# Ind_current_sensor_VW.net
KiCad netlist of a schematic drawn in Altium Designer
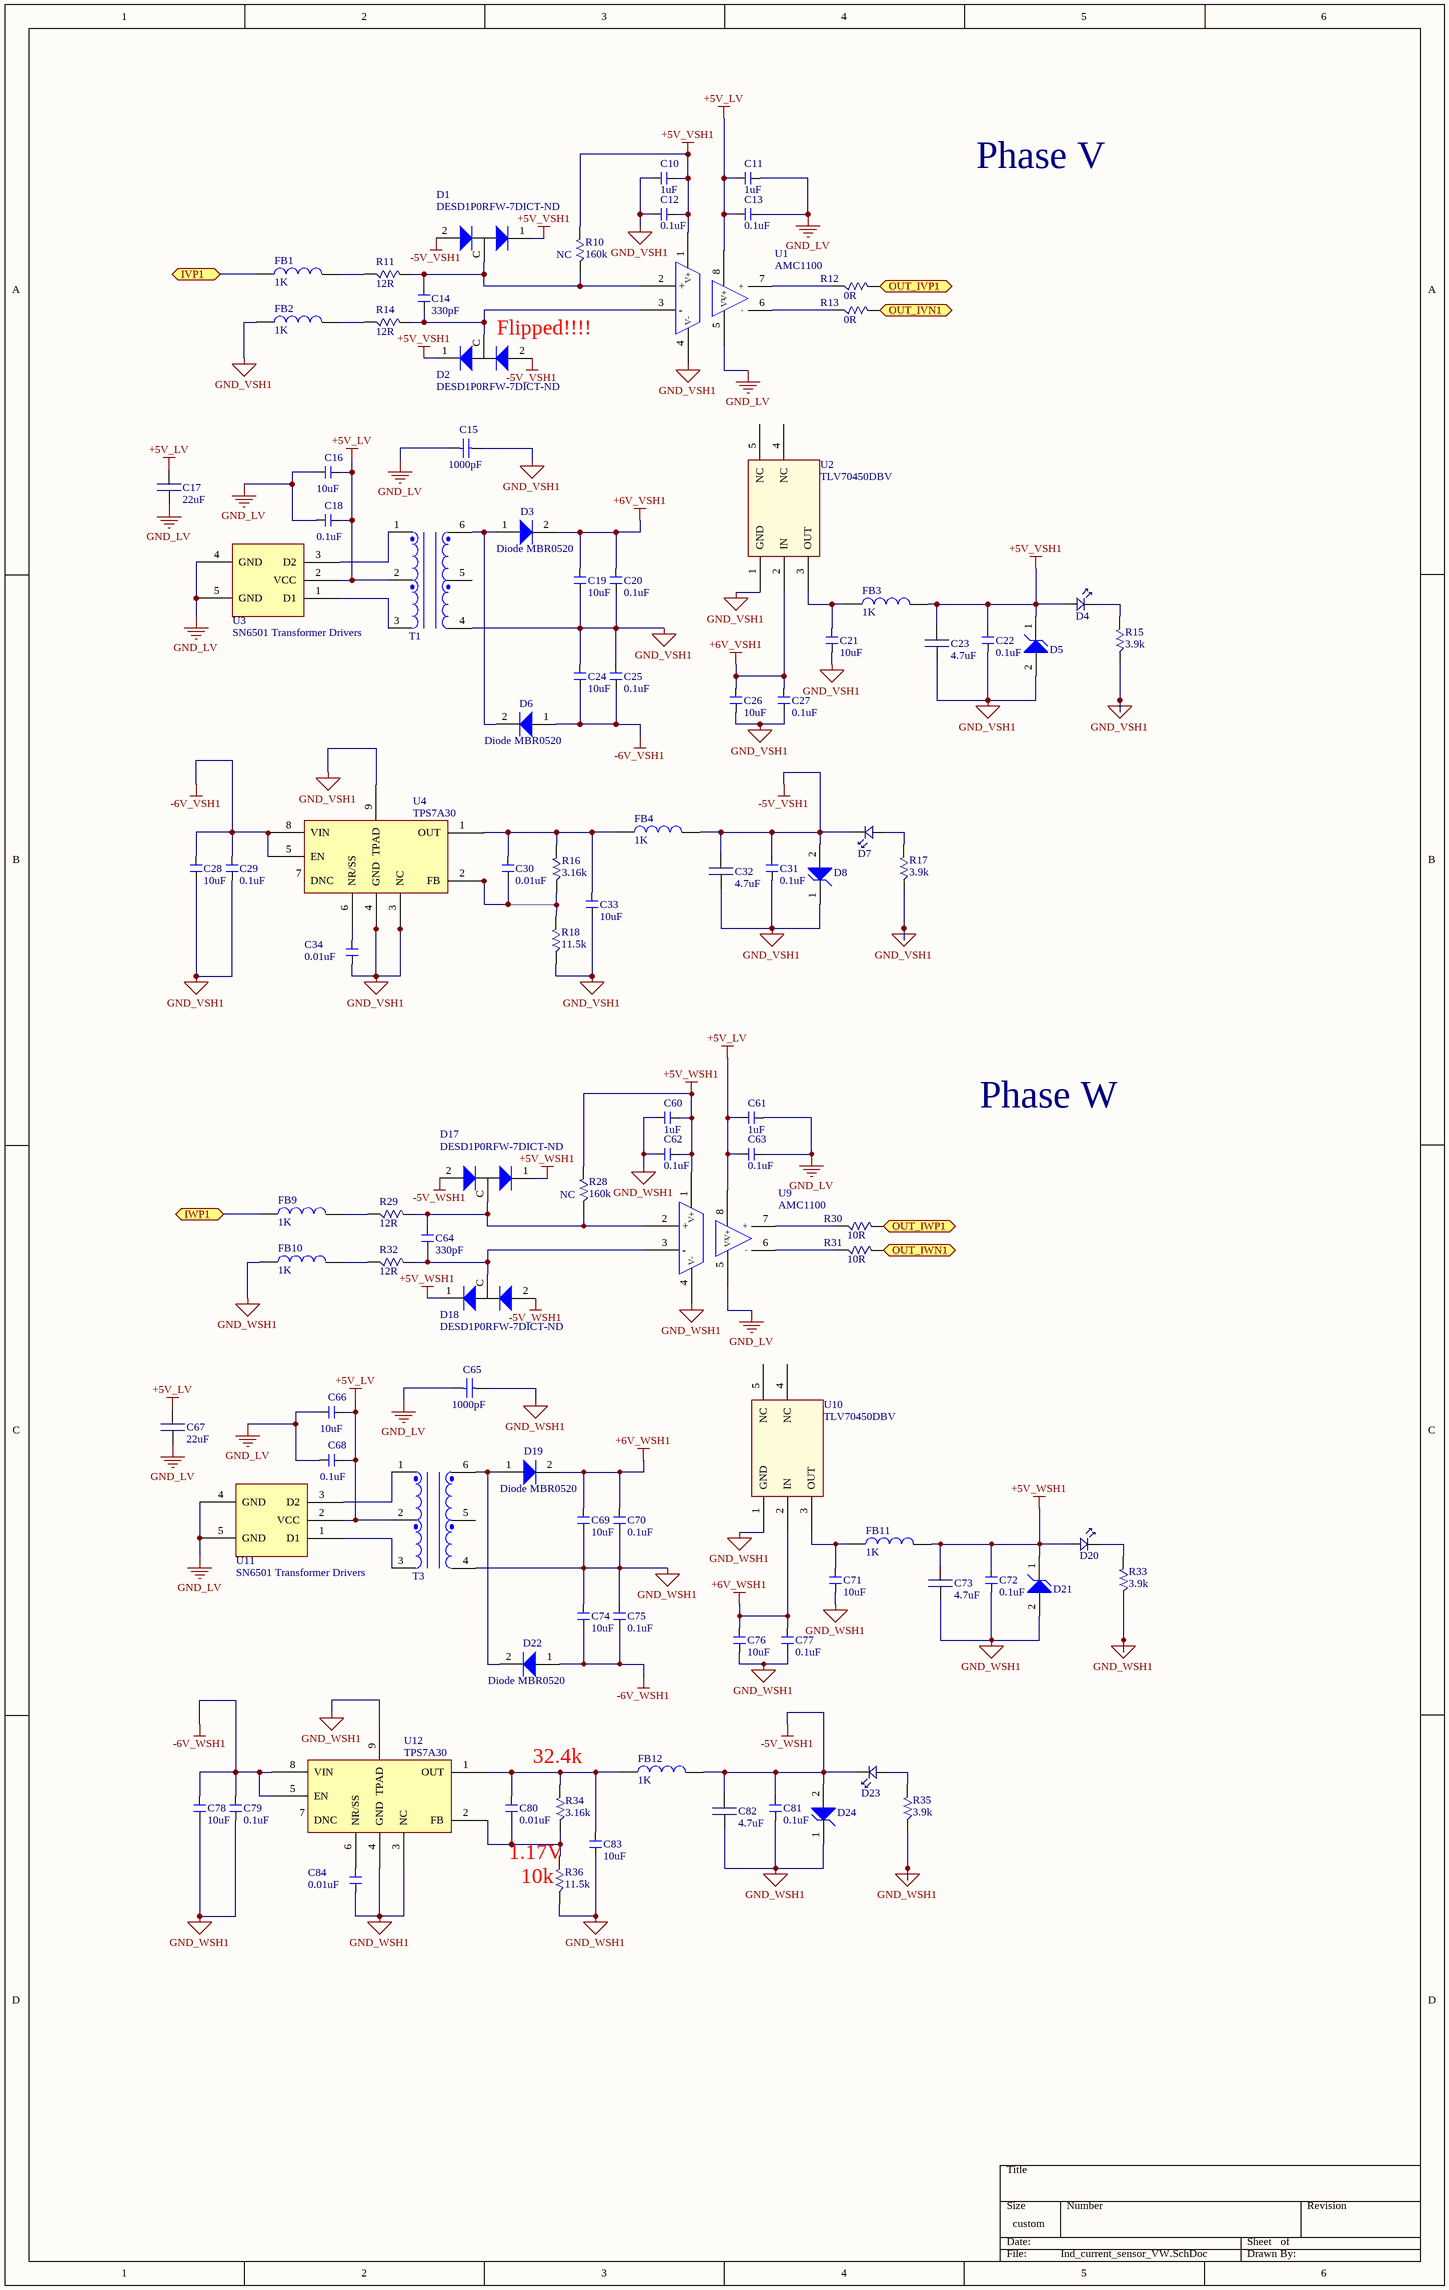
[diagram p0: Ind_current_sensor_VW.SchDoc]

(export (version "E")
  (design (tool "Eeschema 10.0.6"))
  (components
    (comp (ref "C10")
      (value "1uF")
      (footprint "0603 (1608 Metric)")
      (description "CAP CER 1UF 50V X5R 0603")
      (fields (field (name "PART") "1276-1860-1-ND") (field (name "Comment") "Cap 0603_new"))
      (libsource (lib "Library_Microgrid") (part "Cap 0603_new"))
    )
    (comp (ref "C11")
      (value "1uF")
      (footprint "0603 (1608 Metric)")
      (description "CAP CER 1UF 50V X5R 0603")
      (fields (field (name "PART") "1276-1860-1-ND") (field (name "Comment") "Cap 0603_new"))
      (libsource (lib "Library_Microgrid") (part "Cap 0603_new"))
    )
    (comp (ref "C12")
      (value "0.1uF")
      (footprint "0603 (1608 Metric)")
      (description "CAP CER 0.1UF 50V Y5V 0603")
      (fields (field (name "PART") "311-1343-6-ND") (field (name "Comment") "Cap 0603_new"))
      (libsource (lib "Library_Microgrid") (part "Cap 0603_new"))
    )
    (comp (ref "C13")
      (value "0.1uF")
      (footprint "0603 (1608 Metric)")
      (description "CAP CER 0.1UF 50V Y5V 0603")
      (fields (field (name "PART") "311-1343-6-ND") (field (name "Comment") "Cap 0603_new"))
      (libsource (lib "Library_Microgrid") (part "Cap 0603_new"))
    )
    (comp (ref "C14")
      (value "330pF")
      (footprint "0603 (1608 Metric)")
      (description "CAP CER 330PF 50V C0G 0603")
      (fields (field (name "PART") "445-7033-2-ND") (field (name "Comment") "Cap 0603_new"))
      (libsource (lib "Library_Microgrid") (part "Cap 0603_new"))
    )
    (comp (ref "C15")
      (value "1000pF")
      (footprint "RAD-0.3")
      (description "CAP CER 1000PF 1KV Y5P RADIAL")
      (fields
        (field (name "PART") "1251PH-ND")
        (field (name "Comment") "Cap TH")
        (field (name "PUBLISHER") "Altium Limited")
      )
      (libsource (lib "Miscellaneous Devices") (part "Cap"))
    )
    (comp (ref "C16")
      (value "10uF")
      (footprint "0603 (1608 Metric)")
      (description "CAP CER 10UF 35V X5R 0805")
      (fields (field (name "PART") "490-10515-1-ND") (field (name "Comment") "Cap 0603_new"))
      (libsource (lib "Library_Microgrid") (part "Cap 0603_new"))
    )
    (comp (ref "C17")
      (value "22uF")
      (footprint "0805 (2012 metric)")
      (description "CAP CER 22UF 35V X5R 0805")
      (fields (field (name "PART") "445-14428-1-ND") (field (name "Comment") "Cap 0805"))
      (libsource (lib "Library_Microgrid") (part "Cap 0805"))
    )
    (comp (ref "C18")
      (value "0.1uF")
      (footprint "0603 (1608 Metric)")
      (description "CAP CER 0.1UF 50V Y5V 0603")
      (fields (field (name "PART") "311-1343-6-ND") (field (name "Comment") "Cap 0603_new"))
      (libsource (lib "Library_Microgrid") (part "Cap 0603_new"))
    )
    (comp (ref "C19")
      (value "10uF")
      (footprint "0603 (1608 Metric)")
      (description "CAP CER 10UF 35V X5R 0805")
      (fields (field (name "PART") "490-10515-1-ND") (field (name "Comment") "Cap 0603_new"))
      (libsource (lib "Library_Microgrid") (part "Cap 0603_new"))
    )
    (comp (ref "C20")
      (value "0.1uF")
      (footprint "0603 (1608 Metric)")
      (description "CAP CER 0.1UF 50V Y5V 0603")
      (fields (field (name "PART") "311-1343-6-ND") (field (name "Comment") "Cap 0603_new"))
      (libsource (lib "Library_Microgrid") (part "Cap 0603_new"))
    )
    (comp (ref "C21")
      (value "10uF")
      (footprint "0603 (1608 Metric)")
      (description "CAP CER 10UF 35V X5R 0805")
      (fields (field (name "PART") "490-10515-1-ND") (field (name "Comment") "Cap 0603_new"))
      (libsource (lib "Library_Microgrid") (part "Cap 0603_new"))
    )
    (comp (ref "C22")
      (value "0.1uF")
      (footprint "0603 (1608 Metric)")
      (description "CAP CER 0.1UF 50V Y5V 0603")
      (fields (field (name "PART") "311-1343-6-ND") (field (name "Comment") "Cap 0603_new"))
      (libsource (lib "Library_Microgrid") (part "Cap 0603_new"))
    )
    (comp (ref "C23")
      (value "4.7uF")
      (footprint "0805 (2012 metric)")
      (description "CAP CER 4.7UF 50V X5R 0805")
      (fields (field (name "PART") "445-5980-1-ND") (field (name "Comment") "Cap 0805"))
      (libsource (lib "Library_Microgrid") (part "Cap 0805"))
    )
    (comp (ref "C24")
      (value "10uF")
      (footprint "0603 (1608 Metric)")
      (description "CAP CER 10UF 35V X5R 0805")
      (fields (field (name "PART") "490-10515-1-ND") (field (name "Comment") "Cap 0603_new"))
      (libsource (lib "Library_Microgrid") (part "Cap 0603_new"))
    )
    (comp (ref "C25")
      (value "0.1uF")
      (footprint "0603 (1608 Metric)")
      (description "CAP CER 0.1UF 50V Y5V 0603")
      (fields (field (name "PART") "311-1343-6-ND") (field (name "Comment") "Cap 0603_new"))
      (libsource (lib "Library_Microgrid") (part "Cap 0603_new"))
    )
    (comp (ref "C26")
      (value "10uF")
      (footprint "0603 (1608 Metric)")
      (description "CAP CER 10UF 35V X5R 0805")
      (fields (field (name "PART") "490-10515-1-ND") (field (name "Comment") "Cap 0603_new"))
      (libsource (lib "Library_Microgrid") (part "Cap 0603_new"))
    )
    (comp (ref "C27")
      (value "0.1uF")
      (footprint "0603 (1608 Metric)")
      (description "CAP CER 0.1UF 50V Y5V 0603")
      (fields (field (name "PART") "311-1343-6-ND") (field (name "Comment") "Cap 0603_new"))
      (libsource (lib "Library_Microgrid") (part "Cap 0603_new"))
    )
    (comp (ref "C28")
      (value "10uF")
      (footprint "0603 (1608 Metric)")
      (description "CAP CER 10UF 35V X5R 0805")
      (fields (field (name "PART") "490-10515-1-ND") (field (name "Comment") "Cap 0603_new"))
      (libsource (lib "Library_Microgrid") (part "Cap 0603_new"))
    )
    (comp (ref "C29")
      (value "0.1uF")
      (footprint "0603 (1608 Metric)")
      (description "CAP CER 0.1UF 50V Y5V 0603")
      (fields (field (name "PART") "311-1343-6-ND") (field (name "Comment") "Cap 0603_new"))
      (libsource (lib "Library_Microgrid") (part "Cap 0603_new"))
    )
    (comp (ref "C30")
      (value "0.01uF")
      (footprint "0603 (1608 Metric)")
      (description "CAP CER 10000PF 100V X7R 0603")
      (fields (field (name "PART") "478-7418-1-ND") (field (name "Comment") "Cap 0603_new"))
      (libsource (lib "Library_Microgrid") (part "Cap 0603_new"))
    )
    (comp (ref "C31")
      (value "0.1uF")
      (footprint "0603 (1608 Metric)")
      (description "CAP CER 0.1UF 50V Y5V 0603")
      (fields (field (name "PART") "311-1343-6-ND") (field (name "Comment") "Cap 0603_new"))
      (libsource (lib "Library_Microgrid") (part "Cap 0603_new"))
    )
    (comp (ref "C32")
      (value "4.7uF")
      (footprint "0805 (2012 metric)")
      (description "CAP CER 4.7UF 50V X5R 0805")
      (fields (field (name "PART") "445-5980-1-ND") (field (name "Comment") "Cap 0805"))
      (libsource (lib "Library_Microgrid") (part "Cap 0805"))
    )
    (comp (ref "C33")
      (value "10uF")
      (footprint "0603 (1608 Metric)")
      (description "CAP CER 10UF 35V X5R 0805")
      (fields (field (name "PART") "490-10515-1-ND") (field (name "Comment") "Cap 0603_new"))
      (libsource (lib "Library_Microgrid") (part "Cap 0603_new"))
    )
    (comp (ref "C34")
      (value "0.01uF")
      (footprint "0603 (1608 Metric)")
      (description "CAP CER 10000PF 100V X7R 0603")
      (fields (field (name "PART") "478-7418-1-ND") (field (name "Comment") "Cap 0603_new"))
      (libsource (lib "Library_Microgrid") (part "Cap 0603_new"))
    )
    (comp (ref "C60")
      (value "1uF")
      (footprint "0603 (1608 Metric)")
      (description "CAP CER 1UF 50V X5R 0603")
      (fields (field (name "PART") "1276-1860-1-ND") (field (name "Comment") "Cap 0603_new"))
      (libsource (lib "Library_Microgrid") (part "Cap 0603_new"))
    )
    (comp (ref "C61")
      (value "1uF")
      (footprint "0603 (1608 Metric)")
      (description "CAP CER 1UF 50V X5R 0603")
      (fields (field (name "PART") "1276-1860-1-ND") (field (name "Comment") "Cap 0603_new"))
      (libsource (lib "Library_Microgrid") (part "Cap 0603_new"))
    )
    (comp (ref "C62")
      (value "0.1uF")
      (footprint "0603 (1608 Metric)")
      (description "CAP CER 0.1UF 50V Y5V 0603")
      (fields (field (name "PART") "311-1343-6-ND") (field (name "Comment") "Cap 0603_new"))
      (libsource (lib "Library_Microgrid") (part "Cap 0603_new"))
    )
    (comp (ref "C63")
      (value "0.1uF")
      (footprint "0603 (1608 Metric)")
      (description "CAP CER 0.1UF 50V Y5V 0603")
      (fields (field (name "PART") "311-1343-6-ND") (field (name "Comment") "Cap 0603_new"))
      (libsource (lib "Library_Microgrid") (part "Cap 0603_new"))
    )
    (comp (ref "C64")
      (value "330pF")
      (footprint "0603 (1608 Metric)")
      (description "CAP CER 330PF 50V C0G 0603")
      (fields (field (name "PART") "445-7033-2-ND") (field (name "Comment") "Cap 0603_new"))
      (libsource (lib "Library_Microgrid") (part "Cap 0603_new"))
    )
    (comp (ref "C65")
      (value "1000pF")
      (footprint "RAD-0.3")
      (description "CAP CER 1000PF 1KV Y5P RADIAL")
      (fields
        (field (name "PART") "1251PH-ND")
        (field (name "Comment") "Cap TH")
        (field (name "PUBLISHER") "Altium Limited")
      )
      (libsource (lib "Miscellaneous Devices") (part "Cap"))
    )
    (comp (ref "C66")
      (value "10uF")
      (footprint "0603 (1608 Metric)")
      (description "CAP CER 10UF 35V X5R 0805")
      (fields (field (name "PART") "490-10515-1-ND") (field (name "Comment") "Cap 0603_new"))
      (libsource (lib "Library_Microgrid") (part "Cap 0603_new"))
    )
    (comp (ref "C67")
      (value "22uF")
      (footprint "0805 (2012 metric)")
      (description "CAP CER 22UF 35V X5R 0805")
      (fields (field (name "PART") "445-14428-1-ND") (field (name "Comment") "Cap 0805"))
      (libsource (lib "Library_Microgrid") (part "Cap 0805"))
    )
    (comp (ref "C68")
      (value "0.1uF")
      (footprint "0603 (1608 Metric)")
      (description "CAP CER 0.1UF 50V Y5V 0603")
      (fields (field (name "PART") "311-1343-6-ND") (field (name "Comment") "Cap 0603_new"))
      (libsource (lib "Library_Microgrid") (part "Cap 0603_new"))
    )
    (comp (ref "C69")
      (value "10uF")
      (footprint "0603 (1608 Metric)")
      (description "CAP CER 10UF 35V X5R 0805")
      (fields (field (name "PART") "490-10515-1-ND") (field (name "Comment") "Cap 0603_new"))
      (libsource (lib "Library_Microgrid") (part "Cap 0603_new"))
    )
    (comp (ref "C70")
      (value "0.1uF")
      (footprint "0603 (1608 Metric)")
      (description "CAP CER 0.1UF 50V Y5V 0603")
      (fields (field (name "PART") "311-1343-6-ND") (field (name "Comment") "Cap 0603_new"))
      (libsource (lib "Library_Microgrid") (part "Cap 0603_new"))
    )
    (comp (ref "C71")
      (value "10uF")
      (footprint "0603 (1608 Metric)")
      (description "CAP CER 10UF 35V X5R 0805")
      (fields (field (name "PART") "490-10515-1-ND") (field (name "Comment") "Cap 0603_new"))
      (libsource (lib "Library_Microgrid") (part "Cap 0603_new"))
    )
    (comp (ref "C72")
      (value "0.1uF")
      (footprint "0603 (1608 Metric)")
      (description "CAP CER 0.1UF 50V Y5V 0603")
      (fields (field (name "PART") "311-1343-6-ND") (field (name "Comment") "Cap 0603_new"))
      (libsource (lib "Library_Microgrid") (part "Cap 0603_new"))
    )
    (comp (ref "C73")
      (value "4.7uF")
      (footprint "0805 (2012 metric)")
      (description "CAP CER 4.7UF 50V X5R 0805")
      (fields (field (name "PART") "445-5980-1-ND") (field (name "Comment") "Cap 0805"))
      (libsource (lib "Library_Microgrid") (part "Cap 0805"))
    )
    (comp (ref "C74")
      (value "10uF")
      (footprint "0603 (1608 Metric)")
      (description "CAP CER 10UF 35V X5R 0805")
      (fields (field (name "PART") "490-10515-1-ND") (field (name "Comment") "Cap 0603_new"))
      (libsource (lib "Library_Microgrid") (part "Cap 0603_new"))
    )
    (comp (ref "C75")
      (value "0.1uF")
      (footprint "0603 (1608 Metric)")
      (description "CAP CER 0.1UF 50V Y5V 0603")
      (fields (field (name "PART") "311-1343-6-ND") (field (name "Comment") "Cap 0603_new"))
      (libsource (lib "Library_Microgrid") (part "Cap 0603_new"))
    )
    (comp (ref "C76")
      (value "10uF")
      (footprint "0603 (1608 Metric)")
      (description "CAP CER 10UF 35V X5R 0805")
      (fields (field (name "PART") "490-10515-1-ND") (field (name "Comment") "Cap 0603_new"))
      (libsource (lib "Library_Microgrid") (part "Cap 0603_new"))
    )
    (comp (ref "C77")
      (value "0.1uF")
      (footprint "0603 (1608 Metric)")
      (description "CAP CER 0.1UF 50V Y5V 0603")
      (fields (field (name "PART") "311-1343-6-ND") (field (name "Comment") "Cap 0603_new"))
      (libsource (lib "Library_Microgrid") (part "Cap 0603_new"))
    )
    (comp (ref "C78")
      (value "10uF")
      (footprint "0603 (1608 Metric)")
      (description "CAP CER 10UF 35V X5R 0805")
      (fields (field (name "PART") "490-10515-1-ND") (field (name "Comment") "Cap 0603_new"))
      (libsource (lib "Library_Microgrid") (part "Cap 0603_new"))
    )
    (comp (ref "C79")
      (value "0.1uF")
      (footprint "0603 (1608 Metric)")
      (description "CAP CER 0.1UF 50V Y5V 0603")
      (fields (field (name "PART") "311-1343-6-ND") (field (name "Comment") "Cap 0603_new"))
      (libsource (lib "Library_Microgrid") (part "Cap 0603_new"))
    )
    (comp (ref "C80")
      (value "0.01uF")
      (footprint "0603 (1608 Metric)")
      (description "CAP CER 10000PF 100V X7R 0603")
      (fields (field (name "PART") "478-7418-1-ND") (field (name "Comment") "Cap 0603_new"))
      (libsource (lib "Library_Microgrid") (part "Cap 0603_new"))
    )
    (comp (ref "C81")
      (value "0.1uF")
      (footprint "0603 (1608 Metric)")
      (description "CAP CER 0.1UF 50V Y5V 0603")
      (fields (field (name "PART") "311-1343-6-ND") (field (name "Comment") "Cap 0603_new"))
      (libsource (lib "Library_Microgrid") (part "Cap 0603_new"))
    )
    (comp (ref "C82")
      (value "4.7uF")
      (footprint "0805 (2012 metric)")
      (description "CAP CER 4.7UF 50V X5R 0805")
      (fields (field (name "PART") "445-5980-1-ND") (field (name "Comment") "Cap 0805"))
      (libsource (lib "Library_Microgrid") (part "Cap 0805"))
    )
    (comp (ref "C83")
      (value "10uF")
      (footprint "0603 (1608 Metric)")
      (description "CAP CER 10UF 35V X5R 0805")
      (fields (field (name "PART") "490-10515-1-ND") (field (name "Comment") "Cap 0603_new"))
      (libsource (lib "Library_Microgrid") (part "Cap 0603_new"))
    )
    (comp (ref "C84")
      (value "0.01uF")
      (footprint "0603 (1608 Metric)")
      (description "CAP CER 10000PF 100V X7R 0603")
      (fields (field (name "PART") "478-7418-1-ND") (field (name "Comment") "Cap 0603_new"))
      (libsource (lib "Library_Microgrid") (part "Cap 0603_new"))
    )
    (comp (ref "D1")
      (value "TVS - Diodes")
      (footprint "SOT323_ESD")
      (description "TVS DIODE 70VWM 8VC SOT323")
      (fields (field (name "PART") "DESD1P0RFW-7DICT-ND"))
      (libsource (lib "Library_Microgrid") (part "Diode_ESD"))
    )
    (comp (ref "D2")
      (value "TVS - Diodes")
      (footprint "SOT323_ESD")
      (description "TVS DIODE 70VWM 8VC SOT323")
      (fields (field (name "PART") "DESD1P0RFW-7DICT-ND"))
      (libsource (lib "Library_Microgrid") (part "Diode_ESD"))
    )
    (comp (ref "D3")
      (value "Diode MBR0520")
      (footprint "SOD-123")
      (description "DIODE SCHOTTKY 20V 500MA SOD123")
      (fields (field (name "PART") "MBR0520LT1GOSCT-ND"))
      (libsource (lib "Library_Microgrid") (part "Diode MBR0520"))
    )
    (comp (ref "D4")
      (value "LED")
      (footprint "0805 (2012 Metric) Diode")
      (description "LED 0805")
      (libsource (lib "Library_Microgrid") (part "LED"))
    )
    (comp (ref "D5")
      (value "*")
      (footprint "POWERDI")
      (description "DIODE ZENER POWERDI123")
      (fields (field (name "PART") "MMSZ5228B-FDICT-ND"))
      (libsource (lib "Library_Microgrid") (part "Diode Zener POWERDI123"))
    )
    (comp (ref "D6")
      (value "Diode MBR0520")
      (footprint "SOD-123")
      (description "DIODE SCHOTTKY 20V 500MA SOD123")
      (fields (field (name "PART") "MBR0520LT1GOSCT-ND"))
      (libsource (lib "Library_Microgrid") (part "Diode MBR0520"))
    )
    (comp (ref "D7")
      (value "LED")
      (footprint "0805 (2012 Metric) Diode")
      (description "LED 0805")
      (libsource (lib "Library_Microgrid") (part "LED"))
    )
    (comp (ref "D8")
      (value "*")
      (footprint "POWERDI")
      (description "DIODE ZENER POWERDI123")
      (fields (field (name "PART") "MMSZ5228B-FDICT-ND"))
      (libsource (lib "Library_Microgrid") (part "Diode Zener POWERDI123"))
    )
    (comp (ref "D17")
      (value "TVS - Diodes")
      (footprint "SOT323_ESD")
      (description "TVS DIODE 70VWM 8VC SOT323")
      (fields (field (name "PART") "DESD1P0RFW-7DICT-ND"))
      (libsource (lib "Library_Microgrid") (part "Diode_ESD"))
    )
    (comp (ref "D18")
      (value "TVS - Diodes")
      (footprint "SOT323_ESD")
      (description "TVS DIODE 70VWM 8VC SOT323")
      (fields (field (name "PART") "DESD1P0RFW-7DICT-ND"))
      (libsource (lib "Library_Microgrid") (part "Diode_ESD"))
    )
    (comp (ref "D19")
      (value "Diode MBR0520")
      (footprint "SOD-123")
      (description "DIODE SCHOTTKY 20V 500MA SOD123")
      (fields (field (name "PART") "MBR0520LT1GOSCT-ND"))
      (libsource (lib "Library_Microgrid") (part "Diode MBR0520"))
    )
    (comp (ref "D20")
      (value "LED")
      (footprint "0805 (2012 Metric) Diode")
      (description "LED 0805")
      (libsource (lib "Library_Microgrid") (part "LED"))
    )
    (comp (ref "D21")
      (value "*")
      (footprint "POWERDI")
      (description "DIODE ZENER POWERDI123")
      (fields (field (name "PART") "MMSZ5228B-FDICT-ND"))
      (libsource (lib "Library_Microgrid") (part "Diode Zener POWERDI123"))
    )
    (comp (ref "D22")
      (value "Diode MBR0520")
      (footprint "SOD-123")
      (description "DIODE SCHOTTKY 20V 500MA SOD123")
      (fields (field (name "PART") "MBR0520LT1GOSCT-ND"))
      (libsource (lib "Library_Microgrid") (part "Diode MBR0520"))
    )
    (comp (ref "D23")
      (value "LED")
      (footprint "0805 (2012 Metric) Diode")
      (description "LED 0805")
      (libsource (lib "Library_Microgrid") (part "LED"))
    )
    (comp (ref "D24")
      (value "*")
      (footprint "POWERDI")
      (description "DIODE ZENER POWERDI123")
      (fields (field (name "PART") "MMSZ5228B-FDICT-ND"))
      (libsource (lib "Library_Microgrid") (part "Diode Zener POWERDI123"))
    )
    (comp (ref "FB1")
      (value "1K")
      (footprint "0603 (1608 Metric)")
      (description "FERRITE BEAD 1 KOHM 0603 1LN")
      (fields (field (name "PART") "445-8672-1-ND") (field (name "Comment") "Ferrite bead"))
      (libsource (lib "Library_Microgrid") (part "Ferrite bead"))
    )
    (comp (ref "FB2")
      (value "1K")
      (footprint "0603 (1608 Metric)")
      (description "FERRITE BEAD 1 KOHM 0603 1LN")
      (fields (field (name "PART") "445-8672-1-ND") (field (name "Comment") "Ferrite bead"))
      (libsource (lib "Library_Microgrid") (part "Ferrite bead"))
    )
    (comp (ref "FB3")
      (value "1K")
      (footprint "0603 (1608 Metric)")
      (description "FERRITE BEAD 1 KOHM 0603 1LN")
      (fields (field (name "PART") "445-8672-1-ND") (field (name "Comment") "Ferrite bead"))
      (libsource (lib "Library_Microgrid") (part "Ferrite bead"))
    )
    (comp (ref "FB4")
      (value "1K")
      (footprint "0603 (1608 Metric)")
      (description "FERRITE BEAD 1 KOHM 0603 1LN")
      (fields (field (name "PART") "445-8672-1-ND") (field (name "Comment") "Ferrite bead"))
      (libsource (lib "Library_Microgrid") (part "Ferrite bead"))
    )
    (comp (ref "FB9")
      (value "1K")
      (footprint "0603 (1608 Metric)")
      (description "FERRITE BEAD 1 KOHM 0603 1LN")
      (fields (field (name "PART") "445-8672-1-ND") (field (name "Comment") "Ferrite bead"))
      (libsource (lib "Library_Microgrid") (part "Ferrite bead"))
    )
    (comp (ref "FB10")
      (value "1K")
      (footprint "0603 (1608 Metric)")
      (description "FERRITE BEAD 1 KOHM 0603 1LN")
      (fields (field (name "PART") "445-8672-1-ND") (field (name "Comment") "Ferrite bead"))
      (libsource (lib "Library_Microgrid") (part "Ferrite bead"))
    )
    (comp (ref "FB11")
      (value "1K")
      (footprint "0603 (1608 Metric)")
      (description "FERRITE BEAD 1 KOHM 0603 1LN")
      (fields (field (name "PART") "445-8672-1-ND") (field (name "Comment") "Ferrite bead"))
      (libsource (lib "Library_Microgrid") (part "Ferrite bead"))
    )
    (comp (ref "FB12")
      (value "1K")
      (footprint "0603 (1608 Metric)")
      (description "FERRITE BEAD 1 KOHM 0603 1LN")
      (fields (field (name "PART") "445-8672-1-ND") (field (name "Comment") "Ferrite bead"))
      (libsource (lib "Library_Microgrid") (part "Ferrite bead"))
    )
    (comp (ref "R10")
      (value "NC")
      (footprint "0603 (1608 Metric)")
      (description "Resistor 0603")
      (fields (field (name "ALTIUM_VALUE") "160k"))
      (libsource (lib "Library_Microgrid") (part "Resistor 0603"))
    )
    (comp (ref "R11")
      (value "12R")
      (footprint "1206")
      (description "12 Ohm ±0.5% 0.25W, 1/4W Chip Resistor 1206")
      (fields (field (name "PART") "311-2961-1-ND") (field (name "Comment") "Resistor 1206"))
      (libsource (lib "Library_Microgrid") (part "Resistor 1206"))
    )
    (comp (ref "R12")
      (value "0R")
      (footprint "0603 (1608 Metric)")
      (description "RES SMD 10 OHM 0.05% 1/10W 0603")
      (fields (field (name "PART") "RNCF0603AKT10R0CT-ND") (field (name "Comment") "Resistor 0603"))
      (libsource (lib "Library_Microgrid") (part "Resistor 0603"))
    )
    (comp (ref "R13")
      (value "0R")
      (footprint "0603 (1608 Metric)")
      (description "RES SMD 10 OHM 0.05% 1/10W 0603")
      (fields (field (name "PART") "RNCF0603AKT10R0CT-ND") (field (name "Comment") "Resistor 0603"))
      (libsource (lib "Library_Microgrid") (part "Resistor 0603"))
    )
    (comp (ref "R14")
      (value "12R")
      (footprint "1206")
      (description "12 Ohm ±0.5% 0.25W, 1/4W Chip Resistor 1206")
      (fields (field (name "PART") "311-2961-1-ND") (field (name "Comment") "Resistor 1206"))
      (libsource (lib "Library_Microgrid") (part "Resistor 1206"))
    )
    (comp (ref "R15")
      (value "3.9k")
      (footprint "0603 (1608 Metric)")
      (description "RES SMD 3.9K OHM 5% 1/10W 0603")
      (fields (field (name "PART") "541-3.9KGCT-ND") (field (name "Comment") "Resistor 0603"))
      (libsource (lib "Library_Microgrid") (part "Resistor 0603"))
    )
    (comp (ref "R16")
      (value "3.16k")
      (footprint "0603 (1608 Metric)")
      (description "RES SMD 3.16K OHM 1% 1/10W 0603")
      (fields (field (name "PART") "311-3.16KHRCT-ND") (field (name "Comment") "Resistor 0603"))
      (libsource (lib "Library_Microgrid") (part "Resistor 0603"))
    )
    (comp (ref "R17")
      (value "3.9k")
      (footprint "0603 (1608 Metric)")
      (description "RES SMD 3.9K OHM 5% 1/10W 0603")
      (fields (field (name "PART") "541-3.9KGCT-ND") (field (name "Comment") "Resistor 0603"))
      (libsource (lib "Library_Microgrid") (part "Resistor 0603"))
    )
    (comp (ref "R18")
      (value "11.5k")
      (footprint "0603 (1608 Metric)")
      (description "RES SMD 11.5K OHM 1% 1/10W 0603")
      (fields (field (name "PART") "541-11.5KHCT-ND") (field (name "Comment") "Resistor 0603"))
      (libsource (lib "Library_Microgrid") (part "Resistor 0603"))
    )
    (comp (ref "R28")
      (value "NC")
      (footprint "0603 (1608 Metric)")
      (description "Resistor 0603")
      (fields (field (name "ALTIUM_VALUE") "160k"))
      (libsource (lib "Library_Microgrid") (part "Resistor 0603"))
    )
    (comp (ref "R29")
      (value "12R")
      (footprint "1206")
      (description "12 Ohm ±0.5% 0.25W, 1/4W Chip Resistor 1206")
      (fields (field (name "PART") "311-2961-1-ND") (field (name "Comment") "Resistor 1206"))
      (libsource (lib "Library_Microgrid") (part "Resistor 1206"))
    )
    (comp (ref "R30")
      (value "10R")
      (footprint "0603 (1608 Metric)")
      (description "RES SMD 10 OHM 0.05% 1/10W 0603")
      (fields (field (name "PART") "RNCF0603AKT10R0CT-ND") (field (name "Comment") "Resistor 0603"))
      (libsource (lib "Library_Microgrid") (part "Resistor 0603"))
    )
    (comp (ref "R31")
      (value "10R")
      (footprint "0603 (1608 Metric)")
      (description "RES SMD 10 OHM 0.05% 1/10W 0603")
      (fields (field (name "PART") "RNCF0603AKT10R0CT-ND") (field (name "Comment") "Resistor 0603"))
      (libsource (lib "Library_Microgrid") (part "Resistor 0603"))
    )
    (comp (ref "R32")
      (value "12R")
      (footprint "1206")
      (description "12 Ohm ±0.5% 0.25W, 1/4W Chip Resistor 1206")
      (fields (field (name "PART") "311-2961-1-ND") (field (name "Comment") "Resistor 1206"))
      (libsource (lib "Library_Microgrid") (part "Resistor 1206"))
    )
    (comp (ref "R33")
      (value "3.9k")
      (footprint "0603 (1608 Metric)")
      (description "RES SMD 3.9K OHM 5% 1/10W 0603")
      (fields (field (name "PART") "541-3.9KGCT-ND") (field (name "Comment") "Resistor 0603"))
      (libsource (lib "Library_Microgrid") (part "Resistor 0603"))
    )
    (comp (ref "R34")
      (value "3.16k")
      (footprint "0603 (1608 Metric)")
      (description "RES SMD 3.16K OHM 1% 1/10W 0603")
      (fields (field (name "PART") "311-3.16KHRCT-ND") (field (name "Comment") "Resistor 0603"))
      (libsource (lib "Library_Microgrid") (part "Resistor 0603"))
    )
    (comp (ref "R35")
      (value "3.9k")
      (footprint "0603 (1608 Metric)")
      (description "RES SMD 3.9K OHM 5% 1/10W 0603")
      (fields (field (name "PART") "541-3.9KGCT-ND") (field (name "Comment") "Resistor 0603"))
      (libsource (lib "Library_Microgrid") (part "Resistor 0603"))
    )
    (comp (ref "R36")
      (value "11.5k")
      (footprint "0603 (1608 Metric)")
      (description "RES SMD 11.5K OHM 1% 1/10W 0603")
      (fields (field (name "PART") "541-11.5KHCT-ND") (field (name "Comment") "Resistor 0603"))
      (libsource (lib "Library_Microgrid") (part "Resistor 0603"))
    )
    (comp (ref "T1")
      (value "750313769")
      (footprint "Xmr SN6501")
      (description "TRANSFORMER SMD TR1.7 SN6501")
      (fields (field (name "PART") "1297-1107-1-ND"))
      (libsource (lib "Library_Microgrid") (part "750313769"))
    )
    (comp (ref "T3")
      (value "750313769")
      (footprint "Xmr SN6501")
      (description "TRANSFORMER SMD TR1.7 SN6501")
      (fields (field (name "PART") "1297-1107-1-ND"))
      (libsource (lib "Library_Microgrid") (part "750313769"))
    )
    (comp (ref "U1")
      (value "AMC1100")
      (footprint "SOIC8")
      (description "IC OPAMP ISOLATION 100KHZ 8SOIC")
      (fields (field (name "PART") "296-38822-5-ND"))
      (libsource (lib "Library_Microgrid") (part "AMC1100"))
    )
    (comp (ref "U2")
      (value "TLV70450DBV")
      (footprint "SOT23-5")
      (description "IC REG LDO 5V 0.15A SOT23-5")
      (fields (field (name "PART") "296-39287-1-ND"))
      (libsource (lib "Library_Microgrid") (part "TLV70450DBV"))
    )
    (comp (ref "U3")
      (value "SN6501 Transformer Drivers")
      (footprint "SOT23-5")
      (description "IC REG CONV PWR SUPPLIES SOT23-5")
      (fields (field (name "PART") "296-37700-1-ND"))
      (libsource (lib "Library_Microgrid") (part "SN6501"))
    )
    (comp (ref "U4")
      (value "TPS7A30")
      (footprint "8-TSSOP")
      (description "IC REG LDO NEG ADJ 0.2A 8MSOP")
      (fields (field (name "PART") "296-27750-1-ND"))
      (libsource (lib "Library_Microgrid") (part "TPS7A30"))
    )
    (comp (ref "U9")
      (value "AMC1100")
      (footprint "SOIC8")
      (description "IC OPAMP ISOLATION 100KHZ 8SOIC")
      (fields (field (name "PART") "296-38822-5-ND"))
      (libsource (lib "Library_Microgrid") (part "AMC1100"))
    )
    (comp (ref "U10")
      (value "TLV70450DBV")
      (footprint "SOT23-5")
      (description "IC REG LDO 5V 0.15A SOT23-5")
      (fields (field (name "PART") "296-39287-1-ND"))
      (libsource (lib "Library_Microgrid") (part "TLV70450DBV"))
    )
    (comp (ref "U11")
      (value "SN6501 Transformer Drivers")
      (footprint "SOT23-5")
      (description "IC REG CONV PWR SUPPLIES SOT23-5")
      (fields (field (name "PART") "296-37700-1-ND"))
      (libsource (lib "Library_Microgrid") (part "SN6501"))
    )
    (comp (ref "U12")
      (value "TPS7A30")
      (footprint "8-TSSOP")
      (description "IC REG LDO NEG ADJ 0.2A 8MSOP")
      (fields (field (name "PART") "296-27750-1-ND"))
      (libsource (lib "Library_Microgrid") (part "TPS7A30"))
    )
  )
  (nets
    (net (code "1") (name "+5V_LV") (class "Default")
      (node (ref "C11") (pin "1") (pinfunction "OUT_1") (pintype "passive"))
      (node (ref "C13") (pin "1") (pinfunction "OUT_1") (pintype "passive"))
      (node (ref "C16") (pin "2") (pinfunction "OUT_2") (pintype "passive"))
      (node (ref "C17") (pin "2") (pinfunction "OUT_2") (pintype "passive"))
      (node (ref "C18") (pin "2") (pinfunction "OUT_2") (pintype "passive"))
      (node (ref "C61") (pin "1") (pinfunction "OUT_1") (pintype "passive"))
      (node (ref "C63") (pin "1") (pinfunction "OUT_1") (pintype "passive"))
      (node (ref "C66") (pin "2") (pinfunction "OUT_2") (pintype "passive"))
      (node (ref "C67") (pin "2") (pinfunction "OUT_2") (pintype "passive"))
      (node (ref "C68") (pin "2") (pinfunction "OUT_2") (pintype "passive"))
      (node (ref "T1") (pin "2") (pinfunction "1_2") (pintype "passive"))
      (node (ref "T3") (pin "2") (pinfunction "1_2") (pintype "passive"))
      (node (ref "U1") (pin "8") (pinfunction "V+_8") (pintype "passive"))
      (node (ref "U11") (pin "2") (pinfunction "VCC_2") (pintype "passive"))
      (node (ref "U3") (pin "2") (pinfunction "VCC_2") (pintype "passive"))
      (node (ref "U9") (pin "8") (pinfunction "V+_8") (pintype "passive"))
    )
    (net (code "2") (name "+5V_VSH1") (class "Default")
      (node (ref "C10") (pin "2") (pinfunction "OUT_2") (pintype "passive"))
      (node (ref "C12") (pin "2") (pinfunction "OUT_2") (pintype "passive"))
      (node (ref "C22") (pin "2") (pinfunction "OUT_2") (pintype "passive"))
      (node (ref "C23") (pin "2") (pinfunction "OUT_2") (pintype "passive"))
      (node (ref "D1") (pin "1") (pinfunction "Anode_1") (pintype "passive"))
      (node (ref "D2") (pin "1") (pinfunction "Anode_1") (pintype "passive"))
      (node (ref "D4") (pin "A") (pinfunction "A_A") (pintype "passive"))
      (node (ref "D5") (pin "1") (pinfunction "Anode_1") (pintype "passive"))
      (node (ref "FB3") (pin "2") (pinfunction "OUT_2") (pintype "passive"))
      (node (ref "R10") (pin "2") (pinfunction "A_2") (pintype "passive"))
      (node (ref "U1") (pin "1") (pinfunction "V+_1") (pintype "passive"))
    )
    (net (code "3") (name "+5V_WSH1") (class "Default")
      (node (ref "C60") (pin "2") (pinfunction "OUT_2") (pintype "passive"))
      (node (ref "C62") (pin "2") (pinfunction "OUT_2") (pintype "passive"))
      (node (ref "C72") (pin "2") (pinfunction "OUT_2") (pintype "passive"))
      (node (ref "C73") (pin "2") (pinfunction "OUT_2") (pintype "passive"))
      (node (ref "D17") (pin "1") (pinfunction "Anode_1") (pintype "passive"))
      (node (ref "D18") (pin "1") (pinfunction "Anode_1") (pintype "passive"))
      (node (ref "D20") (pin "A") (pinfunction "A_A") (pintype "passive"))
      (node (ref "D21") (pin "1") (pinfunction "Anode_1") (pintype "passive"))
      (node (ref "FB11") (pin "2") (pinfunction "OUT_2") (pintype "passive"))
      (node (ref "R28") (pin "2") (pinfunction "A_2") (pintype "passive"))
      (node (ref "U9") (pin "1") (pinfunction "V+_1") (pintype "passive"))
    )
    (net (code "4") (name "+6V_VSH1") (class "Default")
      (node (ref "C19") (pin "2") (pinfunction "OUT_2") (pintype "passive"))
      (node (ref "C20") (pin "2") (pinfunction "OUT_2") (pintype "passive"))
      (node (ref "C26") (pin "2") (pinfunction "OUT_2") (pintype "passive"))
      (node (ref "C27") (pin "2") (pinfunction "OUT_2") (pintype "passive"))
      (node (ref "D3") (pin "2") (pinfunction "Anode_2") (pintype "passive"))
      (node (ref "U2") (pin "2") (pinfunction "IN_2") (pintype "passive"))
    )
    (net (code "5") (name "+6V_WSH1") (class "Default")
      (node (ref "C69") (pin "2") (pinfunction "OUT_2") (pintype "passive"))
      (node (ref "C70") (pin "2") (pinfunction "OUT_2") (pintype "passive"))
      (node (ref "C76") (pin "2") (pinfunction "OUT_2") (pintype "passive"))
      (node (ref "C77") (pin "2") (pinfunction "OUT_2") (pintype "passive"))
      (node (ref "D19") (pin "2") (pinfunction "Anode_2") (pintype "passive"))
      (node (ref "U10") (pin "2") (pinfunction "IN_2") (pintype "passive"))
    )
    (net (code "6") (name "-5V_VSH1") (class "Default")
      (node (ref "C31") (pin "2") (pinfunction "OUT_2") (pintype "passive"))
      (node (ref "C32") (pin "2") (pinfunction "OUT_2") (pintype "passive"))
      (node (ref "D1") (pin "2") (pinfunction "Anode_2") (pintype "passive"))
      (node (ref "D2") (pin "2") (pinfunction "Anode_2") (pintype "passive"))
      (node (ref "D7") (pin "K") (pinfunction "K_K") (pintype "passive"))
      (node (ref "D8") (pin "2") (pinfunction "Anode_2") (pintype "passive"))
      (node (ref "FB4") (pin "2") (pinfunction "OUT_2") (pintype "passive"))
    )
    (net (code "7") (name "-5V_WSH1") (class "Default")
      (node (ref "C81") (pin "2") (pinfunction "OUT_2") (pintype "passive"))
      (node (ref "C82") (pin "2") (pinfunction "OUT_2") (pintype "passive"))
      (node (ref "D17") (pin "2") (pinfunction "Anode_2") (pintype "passive"))
      (node (ref "D18") (pin "2") (pinfunction "Anode_2") (pintype "passive"))
      (node (ref "D23") (pin "K") (pinfunction "K_K") (pintype "passive"))
      (node (ref "D24") (pin "2") (pinfunction "Anode_2") (pintype "passive"))
      (node (ref "FB12") (pin "2") (pinfunction "OUT_2") (pintype "passive"))
    )
    (net (code "8") (name "-6V_VSH1") (class "Default")
      (node (ref "C24") (pin "1") (pinfunction "OUT_1") (pintype "passive"))
      (node (ref "C25") (pin "1") (pinfunction "OUT_1") (pintype "passive"))
      (node (ref "C28") (pin "2") (pinfunction "OUT_2") (pintype "passive"))
      (node (ref "C29") (pin "2") (pinfunction "OUT_2") (pintype "passive"))
      (node (ref "D6") (pin "1") (pinfunction "Anode_1") (pintype "passive"))
      (node (ref "U4") (pin "5") (pinfunction "EN_5") (pintype "passive"))
      (node (ref "U4") (pin "8") (pinfunction "VIN_8") (pintype "power_in"))
    )
    (net (code "9") (name "-6V_WSH1") (class "Default")
      (node (ref "C74") (pin "1") (pinfunction "OUT_1") (pintype "passive"))
      (node (ref "C75") (pin "1") (pinfunction "OUT_1") (pintype "passive"))
      (node (ref "C78") (pin "2") (pinfunction "OUT_2") (pintype "passive"))
      (node (ref "C79") (pin "2") (pinfunction "OUT_2") (pintype "passive"))
      (node (ref "D22") (pin "1") (pinfunction "Anode_1") (pintype "passive"))
      (node (ref "U12") (pin "5") (pinfunction "EN_5") (pintype "passive"))
      (node (ref "U12") (pin "8") (pinfunction "VIN_8") (pintype "power_in"))
    )
    (net (code "10") (name "/IVP1") (class "Default")
      (node (ref "FB1") (pin "1") (pinfunction "OUT_1") (pintype "passive"))
    )
    (net (code "11") (name "/IWP1") (class "Default")
      (node (ref "FB9") (pin "1") (pinfunction "OUT_1") (pintype "passive"))
    )
    (net (code "12") (name "/OUT_IVN1") (class "Default")
      (node (ref "R13") (pin "2") (pinfunction "A_2") (pintype "passive"))
    )
    (net (code "13") (name "/OUT_IVP1") (class "Default")
      (node (ref "R12") (pin "2") (pinfunction "A_2") (pintype "passive"))
    )
    (net (code "14") (name "/OUT_IWN1") (class "Default")
      (node (ref "R31") (pin "2") (pinfunction "A_2") (pintype "passive"))
    )
    (net (code "15") (name "/OUT_IWP1") (class "Default")
      (node (ref "R30") (pin "2") (pinfunction "A_2") (pintype "passive"))
    )
    (net (code "16") (name "GND_LV") (class "Default")
      (node (ref "C11") (pin "2") (pinfunction "OUT_2") (pintype "passive"))
      (node (ref "C13") (pin "2") (pinfunction "OUT_2") (pintype "passive"))
      (node (ref "C15") (pin "1") (pinfunction "1_1") (pintype "passive"))
      (node (ref "C16") (pin "1") (pinfunction "OUT_1") (pintype "passive"))
      (node (ref "C17") (pin "1") (pinfunction "OUT_1") (pintype "passive"))
      (node (ref "C18") (pin "1") (pinfunction "OUT_1") (pintype "passive"))
      (node (ref "C61") (pin "2") (pinfunction "OUT_2") (pintype "passive"))
      (node (ref "C63") (pin "2") (pinfunction "OUT_2") (pintype "passive"))
      (node (ref "C65") (pin "1") (pinfunction "1_1") (pintype "passive"))
      (node (ref "C66") (pin "1") (pinfunction "OUT_1") (pintype "passive"))
      (node (ref "C67") (pin "1") (pinfunction "OUT_1") (pintype "passive"))
      (node (ref "C68") (pin "1") (pinfunction "OUT_1") (pintype "passive"))
      (node (ref "U1") (pin "5") (pinfunction "V-_5") (pintype "passive"))
      (node (ref "U11") (pin "4") (pinfunction "GND_4") (pintype "passive"))
      (node (ref "U11") (pin "5") (pinfunction "GND_5") (pintype "passive"))
      (node (ref "U3") (pin "4") (pinfunction "GND_4") (pintype "passive"))
      (node (ref "U3") (pin "5") (pinfunction "GND_5") (pintype "passive"))
      (node (ref "U9") (pin "5") (pinfunction "V-_5") (pintype "passive"))
    )
    (net (code "17") (name "GND_VSH1") (class "Default")
      (node (ref "C10") (pin "1") (pinfunction "OUT_1") (pintype "passive"))
      (node (ref "C12") (pin "1") (pinfunction "OUT_1") (pintype "passive"))
      (node (ref "C15") (pin "2") (pinfunction "2_2") (pintype "passive"))
      (node (ref "C19") (pin "1") (pinfunction "OUT_1") (pintype "passive"))
      (node (ref "C20") (pin "1") (pinfunction "OUT_1") (pintype "passive"))
      (node (ref "C21") (pin "1") (pinfunction "OUT_1") (pintype "passive"))
      (node (ref "C22") (pin "1") (pinfunction "OUT_1") (pintype "passive"))
      (node (ref "C23") (pin "1") (pinfunction "OUT_1") (pintype "passive"))
      (node (ref "C24") (pin "2") (pinfunction "OUT_2") (pintype "passive"))
      (node (ref "C25") (pin "2") (pinfunction "OUT_2") (pintype "passive"))
      (node (ref "C26") (pin "1") (pinfunction "OUT_1") (pintype "passive"))
      (node (ref "C27") (pin "1") (pinfunction "OUT_1") (pintype "passive"))
      (node (ref "C28") (pin "1") (pinfunction "OUT_1") (pintype "passive"))
      (node (ref "C29") (pin "1") (pinfunction "OUT_1") (pintype "passive"))
      (node (ref "C31") (pin "1") (pinfunction "OUT_1") (pintype "passive"))
      (node (ref "C32") (pin "1") (pinfunction "OUT_1") (pintype "passive"))
      (node (ref "C33") (pin "1") (pinfunction "OUT_1") (pintype "passive"))
      (node (ref "C34") (pin "1") (pinfunction "OUT_1") (pintype "passive"))
      (node (ref "D5") (pin "2") (pinfunction "Anode_2") (pintype "passive"))
      (node (ref "D8") (pin "1") (pinfunction "Anode_1") (pintype "passive"))
      (node (ref "FB2") (pin "1") (pinfunction "OUT_1") (pintype "passive"))
      (node (ref "R15") (pin "1") (pinfunction "A_1") (pintype "passive"))
      (node (ref "R17") (pin "1") (pinfunction "A_1") (pintype "passive"))
      (node (ref "R18") (pin "1") (pinfunction "A_1") (pintype "passive"))
      (node (ref "T1") (pin "4") (pinfunction "1_4") (pintype "passive"))
      (node (ref "U1") (pin "4") (pinfunction "V-_4") (pintype "passive"))
      (node (ref "U2") (pin "1") (pinfunction "GND_1") (pintype "passive"))
      (node (ref "U4") (pin "3") (pinfunction "NC_3") (pintype "passive"))
      (node (ref "U4") (pin "4") (pinfunction "GND_4") (pintype "power_in"))
      (node (ref "U4") (pin "9") (pinfunction "TPAD_9") (pintype "power_in"))
    )
    (net (code "18") (name "GND_WSH1") (class "Default")
      (node (ref "C60") (pin "1") (pinfunction "OUT_1") (pintype "passive"))
      (node (ref "C62") (pin "1") (pinfunction "OUT_1") (pintype "passive"))
      (node (ref "C65") (pin "2") (pinfunction "2_2") (pintype "passive"))
      (node (ref "C69") (pin "1") (pinfunction "OUT_1") (pintype "passive"))
      (node (ref "C70") (pin "1") (pinfunction "OUT_1") (pintype "passive"))
      (node (ref "C71") (pin "1") (pinfunction "OUT_1") (pintype "passive"))
      (node (ref "C72") (pin "1") (pinfunction "OUT_1") (pintype "passive"))
      (node (ref "C73") (pin "1") (pinfunction "OUT_1") (pintype "passive"))
      (node (ref "C74") (pin "2") (pinfunction "OUT_2") (pintype "passive"))
      (node (ref "C75") (pin "2") (pinfunction "OUT_2") (pintype "passive"))
      (node (ref "C76") (pin "1") (pinfunction "OUT_1") (pintype "passive"))
      (node (ref "C77") (pin "1") (pinfunction "OUT_1") (pintype "passive"))
      (node (ref "C78") (pin "1") (pinfunction "OUT_1") (pintype "passive"))
      (node (ref "C79") (pin "1") (pinfunction "OUT_1") (pintype "passive"))
      (node (ref "C81") (pin "1") (pinfunction "OUT_1") (pintype "passive"))
      (node (ref "C82") (pin "1") (pinfunction "OUT_1") (pintype "passive"))
      (node (ref "C83") (pin "1") (pinfunction "OUT_1") (pintype "passive"))
      (node (ref "C84") (pin "1") (pinfunction "OUT_1") (pintype "passive"))
      (node (ref "D21") (pin "2") (pinfunction "Anode_2") (pintype "passive"))
      (node (ref "D24") (pin "1") (pinfunction "Anode_1") (pintype "passive"))
      (node (ref "FB10") (pin "1") (pinfunction "OUT_1") (pintype "passive"))
      (node (ref "R33") (pin "1") (pinfunction "A_1") (pintype "passive"))
      (node (ref "R35") (pin "1") (pinfunction "A_1") (pintype "passive"))
      (node (ref "R36") (pin "1") (pinfunction "A_1") (pintype "passive"))
      (node (ref "T3") (pin "4") (pinfunction "1_4") (pintype "passive"))
      (node (ref "U10") (pin "1") (pinfunction "GND_1") (pintype "passive"))
      (node (ref "U12") (pin "3") (pinfunction "NC_3") (pintype "passive"))
      (node (ref "U12") (pin "4") (pinfunction "GND_4") (pintype "power_in"))
      (node (ref "U12") (pin "9") (pinfunction "TPAD_9") (pintype "power_in"))
      (node (ref "U9") (pin "4") (pinfunction "V-_4") (pintype "passive"))
    )
    (net (code "19") (name "Net-(D1-Cathode)") (class "Default")
      (node (ref "C14") (pin "1") (pinfunction "OUT_1") (pintype "passive"))
      (node (ref "D1") (pin "C") (pinfunction "Cathode_C") (pintype "passive"))
      (node (ref "R10") (pin "1") (pinfunction "A_1") (pintype "passive"))
      (node (ref "R11") (pin "2") (pinfunction "A_2") (pintype "passive"))
      (node (ref "U1") (pin "2") (pinfunction "+_2") (pintype "passive"))
    )
    (net (code "20") (name "Net-(D2-Cathode)") (class "Default")
      (node (ref "C14") (pin "2") (pinfunction "OUT_2") (pintype "passive"))
      (node (ref "D2") (pin "C") (pinfunction "Cathode_C") (pintype "passive"))
      (node (ref "R14") (pin "2") (pinfunction "A_2") (pintype "passive"))
      (node (ref "U1") (pin "3") (pinfunction "-_3") (pintype "passive"))
    )
    (net (code "21") (name "Net-(D3-Anode-Pad1)") (class "Default")
      (node (ref "D3") (pin "1") (pinfunction "Anode_1") (pintype "passive"))
      (node (ref "D6") (pin "2") (pinfunction "Anode_2") (pintype "passive"))
      (node (ref "T1") (pin "6") (pinfunction "1_6") (pintype "passive"))
    )
    (net (code "22") (name "Net-(D4-PadK)") (class "Default")
      (node (ref "D4") (pin "K") (pinfunction "K_K") (pintype "passive"))
      (node (ref "R15") (pin "2") (pinfunction "A_2") (pintype "passive"))
    )
    (net (code "23") (name "Net-(D7-PadA)") (class "Default")
      (node (ref "D7") (pin "A") (pinfunction "A_A") (pintype "passive"))
      (node (ref "R17") (pin "2") (pinfunction "A_2") (pintype "passive"))
    )
    (net (code "24") (name "Net-(D17-Cathode)") (class "Default")
      (node (ref "C64") (pin "1") (pinfunction "OUT_1") (pintype "passive"))
      (node (ref "D17") (pin "C") (pinfunction "Cathode_C") (pintype "passive"))
      (node (ref "R28") (pin "1") (pinfunction "A_1") (pintype "passive"))
      (node (ref "R29") (pin "2") (pinfunction "A_2") (pintype "passive"))
      (node (ref "U9") (pin "2") (pinfunction "+_2") (pintype "passive"))
    )
    (net (code "25") (name "Net-(D18-Cathode)") (class "Default")
      (node (ref "C64") (pin "2") (pinfunction "OUT_2") (pintype "passive"))
      (node (ref "D18") (pin "C") (pinfunction "Cathode_C") (pintype "passive"))
      (node (ref "R32") (pin "2") (pinfunction "A_2") (pintype "passive"))
      (node (ref "U9") (pin "3") (pinfunction "-_3") (pintype "passive"))
    )
    (net (code "26") (name "Net-(D19-Anode-Pad1)") (class "Default")
      (node (ref "D19") (pin "1") (pinfunction "Anode_1") (pintype "passive"))
      (node (ref "D22") (pin "2") (pinfunction "Anode_2") (pintype "passive"))
      (node (ref "T3") (pin "6") (pinfunction "1_6") (pintype "passive"))
    )
    (net (code "27") (name "Net-(D20-PadK)") (class "Default")
      (node (ref "D20") (pin "K") (pinfunction "K_K") (pintype "passive"))
      (node (ref "R33") (pin "2") (pinfunction "A_2") (pintype "passive"))
    )
    (net (code "28") (name "Net-(D23-PadA)") (class "Default")
      (node (ref "D23") (pin "A") (pinfunction "A_A") (pintype "passive"))
      (node (ref "R35") (pin "2") (pinfunction "A_2") (pintype "passive"))
    )
    (net (code "29") (name "Net-(FB1-OUT-Pad2)") (class "Default")
      (node (ref "FB1") (pin "2") (pinfunction "OUT_2") (pintype "passive"))
      (node (ref "R11") (pin "1") (pinfunction "A_1") (pintype "passive"))
    )
    (net (code "30") (name "Net-(FB2-OUT-Pad2)") (class "Default")
      (node (ref "FB2") (pin "2") (pinfunction "OUT_2") (pintype "passive"))
      (node (ref "R14") (pin "1") (pinfunction "A_1") (pintype "passive"))
    )
    (net (code "31") (name "Net-(FB9-OUT-Pad2)") (class "Default")
      (node (ref "FB9") (pin "2") (pinfunction "OUT_2") (pintype "passive"))
      (node (ref "R29") (pin "1") (pinfunction "A_1") (pintype "passive"))
    )
    (net (code "32") (name "Net-(FB10-OUT-Pad2)") (class "Default")
      (node (ref "FB10") (pin "2") (pinfunction "OUT_2") (pintype "passive"))
      (node (ref "R32") (pin "1") (pinfunction "A_1") (pintype "passive"))
    )
    (net (code "33") (name "Net-(R12-A-Pad1)") (class "Default")
      (node (ref "R12") (pin "1") (pinfunction "A_1") (pintype "passive"))
      (node (ref "U1") (pin "7") (pinfunction "+_7") (pintype "passive"))
    )
    (net (code "34") (name "Net-(R13-A-Pad1)") (class "Default")
      (node (ref "R13") (pin "1") (pinfunction "A_1") (pintype "passive"))
      (node (ref "U1") (pin "6") (pinfunction "-_6") (pintype "passive"))
    )
    (net (code "35") (name "Net-(R30-A-Pad1)") (class "Default")
      (node (ref "R30") (pin "1") (pinfunction "A_1") (pintype "passive"))
      (node (ref "U9") (pin "7") (pinfunction "+_7") (pintype "passive"))
    )
    (net (code "36") (name "Net-(R31-A-Pad1)") (class "Default")
      (node (ref "R31") (pin "1") (pinfunction "A_1") (pintype "passive"))
      (node (ref "U9") (pin "6") (pinfunction "-_6") (pintype "passive"))
    )
    (net (code "37") (name "Net-(U2-OUT)") (class "Default")
      (node (ref "C21") (pin "2") (pinfunction "OUT_2") (pintype "passive"))
      (node (ref "FB3") (pin "1") (pinfunction "OUT_1") (pintype "passive"))
      (node (ref "U2") (pin "3") (pinfunction "OUT_3") (pintype "passive"))
    )
    (net (code "38") (name "Net-(U3-D1)") (class "Default")
      (node (ref "T1") (pin "3") (pinfunction "1_3") (pintype "passive"))
      (node (ref "U3") (pin "1") (pinfunction "D1_1") (pintype "passive"))
    )
    (net (code "39") (name "Net-(U3-D2)") (class "Default")
      (node (ref "T1") (pin "1") (pinfunction "1_1") (pintype "passive"))
      (node (ref "U3") (pin "3") (pinfunction "D2_3") (pintype "passive"))
    )
    (net (code "40") (name "Net-(U4-FB)") (class "Default")
      (node (ref "C30") (pin "2") (pinfunction "OUT_2") (pintype "passive"))
      (node (ref "R16") (pin "1") (pinfunction "A_1") (pintype "passive"))
      (node (ref "R18") (pin "2") (pinfunction "A_2") (pintype "passive"))
      (node (ref "U4") (pin "2") (pinfunction "FB_2") (pintype "passive"))
    )
    (net (code "41") (name "Net-(U4-NR{slash}SS)") (class "Default")
      (node (ref "C34") (pin "2") (pinfunction "OUT_2") (pintype "passive"))
      (node (ref "U4") (pin "6") (pinfunction "NR/SS_6") (pintype "power_in"))
    )
    (net (code "42") (name "Net-(U4-OUT)") (class "Default")
      (node (ref "C30") (pin "1") (pinfunction "OUT_1") (pintype "passive"))
      (node (ref "C33") (pin "2") (pinfunction "OUT_2") (pintype "passive"))
      (node (ref "FB4") (pin "1") (pinfunction "OUT_1") (pintype "passive"))
      (node (ref "R16") (pin "2") (pinfunction "A_2") (pintype "passive"))
      (node (ref "U4") (pin "1") (pinfunction "OUT_1") (pintype "passive"))
    )
    (net (code "43") (name "Net-(U10-OUT)") (class "Default")
      (node (ref "C71") (pin "2") (pinfunction "OUT_2") (pintype "passive"))
      (node (ref "FB11") (pin "1") (pinfunction "OUT_1") (pintype "passive"))
      (node (ref "U10") (pin "3") (pinfunction "OUT_3") (pintype "passive"))
    )
    (net (code "44") (name "Net-(U11-D1)") (class "Default")
      (node (ref "T3") (pin "3") (pinfunction "1_3") (pintype "passive"))
      (node (ref "U11") (pin "1") (pinfunction "D1_1") (pintype "passive"))
    )
    (net (code "45") (name "Net-(U11-D2)") (class "Default")
      (node (ref "T3") (pin "1") (pinfunction "1_1") (pintype "passive"))
      (node (ref "U11") (pin "3") (pinfunction "D2_3") (pintype "passive"))
    )
    (net (code "46") (name "Net-(U12-FB)") (class "Default")
      (node (ref "C80") (pin "2") (pinfunction "OUT_2") (pintype "passive"))
      (node (ref "R34") (pin "1") (pinfunction "A_1") (pintype "passive"))
      (node (ref "R36") (pin "2") (pinfunction "A_2") (pintype "passive"))
      (node (ref "U12") (pin "2") (pinfunction "FB_2") (pintype "passive"))
    )
    (net (code "47") (name "Net-(U12-NR{slash}SS)") (class "Default")
      (node (ref "C84") (pin "2") (pinfunction "OUT_2") (pintype "passive"))
      (node (ref "U12") (pin "6") (pinfunction "NR/SS_6") (pintype "power_in"))
    )
    (net (code "48") (name "Net-(U12-OUT)") (class "Default")
      (node (ref "C80") (pin "1") (pinfunction "OUT_1") (pintype "passive"))
      (node (ref "C83") (pin "2") (pinfunction "OUT_2") (pintype "passive"))
      (node (ref "FB12") (pin "1") (pinfunction "OUT_1") (pintype "passive"))
      (node (ref "R34") (pin "2") (pinfunction "A_2") (pintype "passive"))
      (node (ref "U12") (pin "1") (pinfunction "OUT_1") (pintype "passive"))
    )
    (net (code "49") (name "unconnected-(T1-1-Pad5)") (class "Default")
      (node (ref "T1") (pin "5") (pinfunction "1_5") (pintype "passive"))
    )
    (net (code "50") (name "unconnected-(T3-1-Pad5)") (class "Default")
      (node (ref "T3") (pin "5") (pinfunction "1_5") (pintype "passive"))
    )
    (net (code "51") (name "unconnected-(U2-NC-Pad4)") (class "Default")
      (node (ref "U2") (pin "4") (pinfunction "NC_4") (pintype "passive"))
    )
    (net (code "52") (name "unconnected-(U2-NC-Pad5)") (class "Default")
      (node (ref "U2") (pin "5") (pinfunction "NC_5") (pintype "passive"))
    )
    (net (code "53") (name "unconnected-(U4-DNC-Pad7)") (class "Default")
      (node (ref "U4") (pin "7") (pinfunction "DNC_7") (pintype "passive"))
    )
    (net (code "54") (name "unconnected-(U10-NC-Pad4)") (class "Default")
      (node (ref "U10") (pin "4") (pinfunction "NC_4") (pintype "passive"))
    )
    (net (code "55") (name "unconnected-(U10-NC-Pad5)") (class "Default")
      (node (ref "U10") (pin "5") (pinfunction "NC_5") (pintype "passive"))
    )
    (net (code "56") (name "unconnected-(U12-DNC-Pad7)") (class "Default")
      (node (ref "U12") (pin "7") (pinfunction "DNC_7") (pintype "passive"))
    )
  )
)
